# Misc.net
KiCad netlist of a schematic drawn in Altium Designer
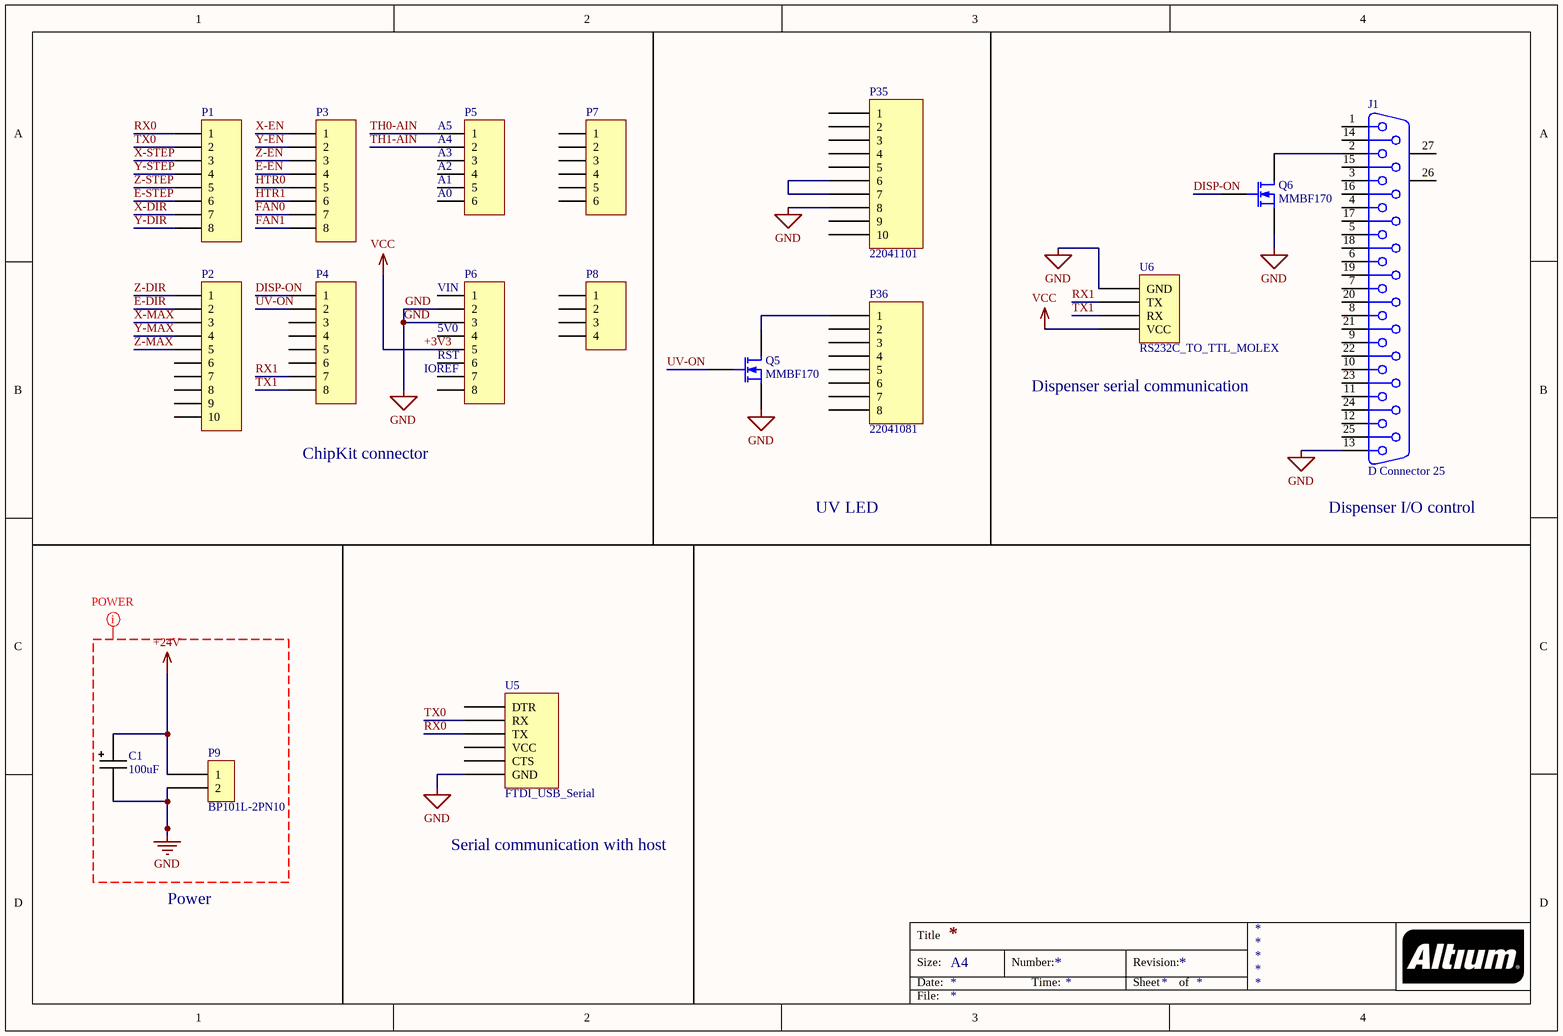
[diagram p0: Misc.SchDoc]

(export (version "E")
  (design (tool "Eeschema 10.0.6"))
  (components
    (comp (ref "C1")
      (value "Cap_alumi_electrolytic")
      (footprint "EEE-1HA101UP")
      (fields (field (name "ALTIUM_UNNAMED_1") "100uF"))
      (libsource (lib "3dprinter_shield") (part "Cap_alumi_electrolytic"))
    )
    (comp (ref "J1")
      (value "D Connector 25")
      (footprint "DSUB1.385-2H25A")
      (description "Receptacle Assembly, 25 Position, Right Angle")
      (fields (field (name "PUBLISHER") "Altium Limited"))
      (libsource (lib "Miscellaneous Connectors") (part "D Connector 25"))
    )
    (comp (ref "P1")
      (value "~")
      (footprint "HDR1X8")
      (description "Header, 8-Pin")
      (fields (field (name "PUBLISHER") "Altium Limited"))
      (libsource (lib "Miscellaneous Connectors") (part "Header 8"))
    )
    (comp (ref "P2")
      (value "~")
      (footprint "HDR1X10")
      (description "Header, 10-Pin")
      (fields (field (name "PUBLISHER") "Altium Limited"))
      (libsource (lib "Miscellaneous Connectors") (part "Header 10"))
    )
    (comp (ref "P3")
      (value "~")
      (footprint "HDR1X8")
      (description "Header, 8-Pin")
      (fields (field (name "PUBLISHER") "Altium Limited"))
      (libsource (lib "Miscellaneous Connectors") (part "Header 8"))
    )
    (comp (ref "P4")
      (value "~")
      (footprint "HDR1X8")
      (description "Header, 8-Pin")
      (fields (field (name "PUBLISHER") "Altium Limited"))
      (libsource (lib "Miscellaneous Connectors") (part "Header 8"))
    )
    (comp (ref "P5")
      (value "~")
      (footprint "HDR1X6")
      (description "Header, 6-Pin")
      (fields (field (name "PUBLISHER") "Altium Limited"))
      (libsource (lib "Miscellaneous Connectors") (part "Header 6"))
    )
    (comp (ref "P6")
      (value "~")
      (footprint "HDR1X8")
      (description "Header, 8-Pin")
      (fields (field (name "PUBLISHER") "Altium Limited"))
      (libsource (lib "Miscellaneous Connectors") (part "Header 8"))
    )
    (comp (ref "P7")
      (value "~")
      (footprint "HDR1X6")
      (description "Header, 6-Pin")
      (fields (field (name "PUBLISHER") "Altium Limited"))
      (libsource (lib "Miscellaneous Connectors") (part "Header 6"))
    )
    (comp (ref "P8")
      (value "Header 4")
      (footprint "HDR1X4")
      (description "Header, 4-Pin")
      (fields (field (name "PUBLISHER") "Altium Limited"))
      (libsource (lib "Miscellaneous Connectors") (part "Header 4"))
    )
    (comp (ref "P9")
      (value "BP101L-2PN10")
      (footprint "BP101L-2PN10")
      (libsource (lib "3dprinter_shield") (part "BP101L-2PN10"))
    )
    (comp (ref "P35")
      (value "22041101")
      (footprint "PHOENIX_10PIN_MOLEX")
      (libsource (lib "3dprinter_shield") (part "Phoenix_10pin_MOLEX"))
    )
    (comp (ref "P36")
      (value "22041081")
      (footprint "PHOENIX_8PIN_MOLEX")
      (libsource (lib "3dprinter_shield") (part "Phoenix_8pin_MOLEX"))
    )
    (comp (ref "Q5")
      (value "MMBF170")
      (footprint "MMBF170-SOT95P240X130-3N")
      (libsource (lib "3dprinter_shield") (part "MMBF170"))
    )
    (comp (ref "Q6")
      (value "MMBF170")
      (footprint "MMBF170-SOT95P240X130-3N")
      (libsource (lib "3dprinter_shield") (part "MMBF170"))
    )
    (comp (ref "U5")
      (value "FTDI_USB_Serial")
      (footprint "FTDI_USB_Serial")
      (libsource (lib "3dprinter_shield") (part "FTDI_USB_Serial"))
    )
    (comp (ref "U6")
      (value "RS232C_TO_TTL_MOLEX")
      (footprint "RS232C_TO_TTL_MOLEX")
      (libsource (lib "3dprinter_shield") (part "RS232C_TO_TTL_MOLEX"))
    )
  )
  (nets
    (net (code "1") (name "+24V") (class "Default")
      (node (ref "C1") (pin "2") (pinfunction "2_2") (pintype "passive"))
      (node (ref "P9") (pin "1") (pinfunction "1_1") (pintype "passive"))
    )
    (net (code "2") (name "/DISP-ON") (class "Default")
      (node (ref "P4") (pin "1") (pinfunction "1_1") (pintype "passive"))
      (node (ref "Q6") (pin "1") (pinfunction "G_1") (pintype "passive"))
    )
    (net (code "3") (name "/E-DIR") (class "Default")
      (node (ref "P2") (pin "2") (pinfunction "2_2") (pintype "passive"))
    )
    (net (code "4") (name "/E-EN") (class "Default")
      (node (ref "P3") (pin "4") (pinfunction "4_4") (pintype "passive"))
    )
    (net (code "5") (name "/E-STEP") (class "Default")
      (node (ref "P1") (pin "6") (pinfunction "6_6") (pintype "passive"))
    )
    (net (code "6") (name "/FAN0") (class "Default")
      (node (ref "P3") (pin "7") (pinfunction "7_7") (pintype "passive"))
    )
    (net (code "7") (name "/FAN1") (class "Default")
      (node (ref "P3") (pin "8") (pinfunction "8_8") (pintype "passive"))
    )
    (net (code "8") (name "/HTR0") (class "Default")
      (node (ref "P3") (pin "5") (pinfunction "5_5") (pintype "passive"))
    )
    (net (code "9") (name "/HTR1") (class "Default")
      (node (ref "P3") (pin "6") (pinfunction "6_6") (pintype "passive"))
    )
    (net (code "10") (name "/RX0") (class "Default")
      (node (ref "P1") (pin "1") (pinfunction "1_1") (pintype "passive"))
      (node (ref "U5") (pin "3") (pinfunction "TX_3") (pintype "passive"))
    )
    (net (code "11") (name "/RX1") (class "Default")
      (node (ref "P4") (pin "7") (pinfunction "7_7") (pintype "passive"))
      (node (ref "U6") (pin "TX") (pinfunction "TX_TX") (pintype "passive"))
    )
    (net (code "12") (name "/TH0-AIN") (class "Default")
      (node (ref "P5") (pin "1") (pinfunction "1_1") (pintype "passive"))
    )
    (net (code "13") (name "/TH1-AIN") (class "Default")
      (node (ref "P5") (pin "2") (pinfunction "2_2") (pintype "passive"))
    )
    (net (code "14") (name "/TX0") (class "Default")
      (node (ref "P1") (pin "2") (pinfunction "2_2") (pintype "passive"))
      (node (ref "U5") (pin "2") (pinfunction "RX_2") (pintype "passive"))
    )
    (net (code "15") (name "/TX1") (class "Default")
      (node (ref "P4") (pin "8") (pinfunction "8_8") (pintype "passive"))
      (node (ref "U6") (pin "RX") (pinfunction "RX_RX") (pintype "passive"))
    )
    (net (code "16") (name "/UV-ON") (class "Default")
      (node (ref "P4") (pin "2") (pinfunction "2_2") (pintype "passive"))
      (node (ref "Q5") (pin "1") (pinfunction "G_1") (pintype "passive"))
    )
    (net (code "17") (name "/X-DIR") (class "Default")
      (node (ref "P1") (pin "7") (pinfunction "7_7") (pintype "passive"))
    )
    (net (code "18") (name "/X-EN") (class "Default")
      (node (ref "P3") (pin "1") (pinfunction "1_1") (pintype "passive"))
    )
    (net (code "19") (name "/X-MAX") (class "Default")
      (node (ref "P2") (pin "3") (pinfunction "3_3") (pintype "passive"))
    )
    (net (code "20") (name "/X-STEP") (class "Default")
      (node (ref "P1") (pin "3") (pinfunction "3_3") (pintype "passive"))
    )
    (net (code "21") (name "/Y-DIR") (class "Default")
      (node (ref "P1") (pin "8") (pinfunction "8_8") (pintype "passive"))
    )
    (net (code "22") (name "/Y-EN") (class "Default")
      (node (ref "P3") (pin "2") (pinfunction "2_2") (pintype "passive"))
    )
    (net (code "23") (name "/Y-MAX") (class "Default")
      (node (ref "P2") (pin "4") (pinfunction "4_4") (pintype "passive"))
    )
    (net (code "24") (name "/Y-STEP") (class "Default")
      (node (ref "P1") (pin "4") (pinfunction "4_4") (pintype "passive"))
    )
    (net (code "25") (name "/Z-DIR") (class "Default")
      (node (ref "P2") (pin "1") (pinfunction "1_1") (pintype "passive"))
    )
    (net (code "26") (name "/Z-EN") (class "Default")
      (node (ref "P3") (pin "3") (pinfunction "3_3") (pintype "passive"))
    )
    (net (code "27") (name "/Z-MAX") (class "Default")
      (node (ref "P2") (pin "5") (pinfunction "5_5") (pintype "passive"))
    )
    (net (code "28") (name "/Z-STEP") (class "Default")
      (node (ref "P1") (pin "5") (pinfunction "5_5") (pintype "passive"))
    )
    (net (code "29") (name "GND") (class "Default")
      (node (ref "C1") (pin "1") (pinfunction "1_1") (pintype "passive"))
      (node (ref "J1") (pin "13") (pinfunction "13_13") (pintype "passive"))
      (node (ref "P35") (pin "8") (pinfunction "8_8") (pintype "passive"))
      (node (ref "P6") (pin "2") (pinfunction "2_2") (pintype "passive"))
      (node (ref "P6") (pin "3") (pinfunction "3_3") (pintype "passive"))
      (node (ref "P9") (pin "2") (pinfunction "2_2") (pintype "passive"))
      (node (ref "Q5") (pin "2") (pinfunction "S_2") (pintype "passive"))
      (node (ref "Q6") (pin "2") (pinfunction "S_2") (pintype "passive"))
      (node (ref "U5") (pin "6") (pinfunction "GND_6") (pintype "passive"))
      (node (ref "U6") (pin "GND") (pinfunction "GND_GND") (pintype "passive"))
    )
    (net (code "30") (name "Net-(P35-Pad6)") (class "Default")
      (node (ref "P35") (pin "6") (pinfunction "6_6") (pintype "passive"))
      (node (ref "P35") (pin "7") (pinfunction "7_7") (pintype "passive"))
    )
    (net (code "31") (name "Net-(Q5-D)") (class "Default")
      (node (ref "P36") (pin "1") (pinfunction "1_1") (pintype "passive"))
      (node (ref "Q5") (pin "3") (pinfunction "D_3") (pintype "passive"))
    )
    (net (code "32") (name "Net-(Q6-D)") (class "Default")
      (node (ref "J1") (pin "2") (pinfunction "2_2") (pintype "passive"))
      (node (ref "Q6") (pin "3") (pinfunction "D_3") (pintype "passive"))
    )
    (net (code "33") (name "VCC") (class "Default")
      (node (ref "P6") (pin "5") (pinfunction "5_5") (pintype "passive"))
      (node (ref "U6") (pin "VCC") (pinfunction "VCC_VCC") (pintype "passive"))
    )
    (net (code "34") (name "unconnected-(J1-MH1-Pad26)") (class "Default")
      (node (ref "J1") (pin "26") (pinfunction "MH1_26") (pintype "passive"))
    )
    (net (code "35") (name "unconnected-(J1-MH2-Pad27)") (class "Default")
      (node (ref "J1") (pin "27") (pinfunction "MH2_27") (pintype "passive"))
    )
    (net (code "36") (name "unconnected-(J1-Pad1)") (class "Default")
      (node (ref "J1") (pin "1") (pinfunction "1_1") (pintype "passive"))
    )
    (net (code "37") (name "unconnected-(J1-Pad3)") (class "Default")
      (node (ref "J1") (pin "3") (pinfunction "3_3") (pintype "passive"))
    )
    (net (code "38") (name "unconnected-(J1-Pad4)") (class "Default")
      (node (ref "J1") (pin "4") (pinfunction "4_4") (pintype "passive"))
    )
    (net (code "39") (name "unconnected-(J1-Pad5)") (class "Default")
      (node (ref "J1") (pin "5") (pinfunction "5_5") (pintype "passive"))
    )
    (net (code "40") (name "unconnected-(J1-Pad6)") (class "Default")
      (node (ref "J1") (pin "6") (pinfunction "6_6") (pintype "passive"))
    )
    (net (code "41") (name "unconnected-(J1-Pad7)") (class "Default")
      (node (ref "J1") (pin "7") (pinfunction "7_7") (pintype "passive"))
    )
    (net (code "42") (name "unconnected-(J1-Pad8)") (class "Default")
      (node (ref "J1") (pin "8") (pinfunction "8_8") (pintype "passive"))
    )
    (net (code "43") (name "unconnected-(J1-Pad9)") (class "Default")
      (node (ref "J1") (pin "9") (pinfunction "9_9") (pintype "passive"))
    )
    (net (code "44") (name "unconnected-(J1-Pad10)") (class "Default")
      (node (ref "J1") (pin "10") (pinfunction "10_10") (pintype "passive"))
    )
    (net (code "45") (name "unconnected-(J1-Pad11)") (class "Default")
      (node (ref "J1") (pin "11") (pinfunction "11_11") (pintype "passive"))
    )
    (net (code "46") (name "unconnected-(J1-Pad12)") (class "Default")
      (node (ref "J1") (pin "12") (pinfunction "12_12") (pintype "passive"))
    )
    (net (code "47") (name "unconnected-(J1-Pad14)") (class "Default")
      (node (ref "J1") (pin "14") (pinfunction "14_14") (pintype "passive"))
    )
    (net (code "48") (name "unconnected-(J1-Pad15)") (class "Default")
      (node (ref "J1") (pin "15") (pinfunction "15_15") (pintype "passive"))
    )
    (net (code "49") (name "unconnected-(J1-Pad16)") (class "Default")
      (node (ref "J1") (pin "16") (pinfunction "16_16") (pintype "passive"))
    )
    (net (code "50") (name "unconnected-(J1-Pad17)") (class "Default")
      (node (ref "J1") (pin "17") (pinfunction "17_17") (pintype "passive"))
    )
    (net (code "51") (name "unconnected-(J1-Pad18)") (class "Default")
      (node (ref "J1") (pin "18") (pinfunction "18_18") (pintype "passive"))
    )
    (net (code "52") (name "unconnected-(J1-Pad19)") (class "Default")
      (node (ref "J1") (pin "19") (pinfunction "19_19") (pintype "passive"))
    )
    (net (code "53") (name "unconnected-(J1-Pad20)") (class "Default")
      (node (ref "J1") (pin "20") (pinfunction "20_20") (pintype "passive"))
    )
    (net (code "54") (name "unconnected-(J1-Pad21)") (class "Default")
      (node (ref "J1") (pin "21") (pinfunction "21_21") (pintype "passive"))
    )
    (net (code "55") (name "unconnected-(J1-Pad22)") (class "Default")
      (node (ref "J1") (pin "22") (pinfunction "22_22") (pintype "passive"))
    )
    (net (code "56") (name "unconnected-(J1-Pad23)") (class "Default")
      (node (ref "J1") (pin "23") (pinfunction "23_23") (pintype "passive"))
    )
    (net (code "57") (name "unconnected-(J1-Pad24)") (class "Default")
      (node (ref "J1") (pin "24") (pinfunction "24_24") (pintype "passive"))
    )
    (net (code "58") (name "unconnected-(J1-Pad25)") (class "Default")
      (node (ref "J1") (pin "25") (pinfunction "25_25") (pintype "passive"))
    )
    (net (code "59") (name "unconnected-(P2-Pad6)") (class "Default")
      (node (ref "P2") (pin "6") (pinfunction "6_6") (pintype "passive"))
    )
    (net (code "60") (name "unconnected-(P2-Pad7)") (class "Default")
      (node (ref "P2") (pin "7") (pinfunction "7_7") (pintype "passive"))
    )
    (net (code "61") (name "unconnected-(P2-Pad8)") (class "Default")
      (node (ref "P2") (pin "8") (pinfunction "8_8") (pintype "passive"))
    )
    (net (code "62") (name "unconnected-(P2-Pad9)") (class "Default")
      (node (ref "P2") (pin "9") (pinfunction "9_9") (pintype "passive"))
    )
    (net (code "63") (name "unconnected-(P2-Pad10)") (class "Default")
      (node (ref "P2") (pin "10") (pinfunction "10_10") (pintype "passive"))
    )
    (net (code "64") (name "unconnected-(P4-Pad3)") (class "Default")
      (node (ref "P4") (pin "3") (pinfunction "3_3") (pintype "passive"))
    )
    (net (code "65") (name "unconnected-(P4-Pad4)") (class "Default")
      (node (ref "P4") (pin "4") (pinfunction "4_4") (pintype "passive"))
    )
    (net (code "66") (name "unconnected-(P4-Pad5)") (class "Default")
      (node (ref "P4") (pin "5") (pinfunction "5_5") (pintype "passive"))
    )
    (net (code "67") (name "unconnected-(P4-Pad6)") (class "Default")
      (node (ref "P4") (pin "6") (pinfunction "6_6") (pintype "passive"))
    )
    (net (code "68") (name "unconnected-(P5-Pad3)") (class "Default")
      (node (ref "P5") (pin "3") (pinfunction "3_3") (pintype "passive"))
    )
    (net (code "69") (name "unconnected-(P5-Pad4)") (class "Default")
      (node (ref "P5") (pin "4") (pinfunction "4_4") (pintype "passive"))
    )
    (net (code "70") (name "unconnected-(P5-Pad5)") (class "Default")
      (node (ref "P5") (pin "5") (pinfunction "5_5") (pintype "passive"))
    )
    (net (code "71") (name "unconnected-(P5-Pad6)") (class "Default")
      (node (ref "P5") (pin "6") (pinfunction "6_6") (pintype "passive"))
    )
    (net (code "72") (name "unconnected-(P6-Pad1)") (class "Default")
      (node (ref "P6") (pin "1") (pinfunction "1_1") (pintype "passive"))
    )
    (net (code "73") (name "unconnected-(P6-Pad4)") (class "Default")
      (node (ref "P6") (pin "4") (pinfunction "4_4") (pintype "passive"))
    )
    (net (code "74") (name "unconnected-(P6-Pad6)") (class "Default")
      (node (ref "P6") (pin "6") (pinfunction "6_6") (pintype "passive"))
    )
    (net (code "75") (name "unconnected-(P6-Pad7)") (class "Default")
      (node (ref "P6") (pin "7") (pinfunction "7_7") (pintype "passive"))
    )
    (net (code "76") (name "unconnected-(P6-Pad8)") (class "Default")
      (node (ref "P6") (pin "8") (pinfunction "8_8") (pintype "passive"))
    )
    (net (code "77") (name "unconnected-(P7-Pad1)") (class "Default")
      (node (ref "P7") (pin "1") (pinfunction "1_1") (pintype "passive"))
    )
    (net (code "78") (name "unconnected-(P7-Pad2)") (class "Default")
      (node (ref "P7") (pin "2") (pinfunction "2_2") (pintype "passive"))
    )
    (net (code "79") (name "unconnected-(P7-Pad3)") (class "Default")
      (node (ref "P7") (pin "3") (pinfunction "3_3") (pintype "passive"))
    )
    (net (code "80") (name "unconnected-(P7-Pad4)") (class "Default")
      (node (ref "P7") (pin "4") (pinfunction "4_4") (pintype "passive"))
    )
    (net (code "81") (name "unconnected-(P7-Pad5)") (class "Default")
      (node (ref "P7") (pin "5") (pinfunction "5_5") (pintype "passive"))
    )
    (net (code "82") (name "unconnected-(P7-Pad6)") (class "Default")
      (node (ref "P7") (pin "6") (pinfunction "6_6") (pintype "passive"))
    )
    (net (code "83") (name "unconnected-(P8-Pad1)") (class "Default")
      (node (ref "P8") (pin "1") (pinfunction "1_1") (pintype "passive"))
    )
    (net (code "84") (name "unconnected-(P8-Pad2)") (class "Default")
      (node (ref "P8") (pin "2") (pinfunction "2_2") (pintype "passive"))
    )
    (net (code "85") (name "unconnected-(P8-Pad3)") (class "Default")
      (node (ref "P8") (pin "3") (pinfunction "3_3") (pintype "passive"))
    )
    (net (code "86") (name "unconnected-(P8-Pad4)") (class "Default")
      (node (ref "P8") (pin "4") (pinfunction "4_4") (pintype "passive"))
    )
    (net (code "87") (name "unconnected-(P35-Pad1)") (class "Default")
      (node (ref "P35") (pin "1") (pinfunction "1_1") (pintype "passive"))
    )
    (net (code "88") (name "unconnected-(P35-Pad2)") (class "Default")
      (node (ref "P35") (pin "2") (pinfunction "2_2") (pintype "passive"))
    )
    (net (code "89") (name "unconnected-(P35-Pad3)") (class "Default")
      (node (ref "P35") (pin "3") (pinfunction "3_3") (pintype "passive"))
    )
    (net (code "90") (name "unconnected-(P35-Pad4)") (class "Default")
      (node (ref "P35") (pin "4") (pinfunction "4_4") (pintype "passive"))
    )
    (net (code "91") (name "unconnected-(P35-Pad5)") (class "Default")
      (node (ref "P35") (pin "5") (pinfunction "5_5") (pintype "passive"))
    )
    (net (code "92") (name "unconnected-(P35-Pad9)") (class "Default")
      (node (ref "P35") (pin "9") (pinfunction "9_9") (pintype "passive"))
    )
    (net (code "93") (name "unconnected-(P35-Pad10)") (class "Default")
      (node (ref "P35") (pin "10") (pinfunction "10_10") (pintype "passive"))
    )
    (net (code "94") (name "unconnected-(P36-Pad2)") (class "Default")
      (node (ref "P36") (pin "2") (pinfunction "2_2") (pintype "passive"))
    )
    (net (code "95") (name "unconnected-(P36-Pad3)") (class "Default")
      (node (ref "P36") (pin "3") (pinfunction "3_3") (pintype "passive"))
    )
    (net (code "96") (name "unconnected-(P36-Pad4)") (class "Default")
      (node (ref "P36") (pin "4") (pinfunction "4_4") (pintype "passive"))
    )
    (net (code "97") (name "unconnected-(P36-Pad5)") (class "Default")
      (node (ref "P36") (pin "5") (pinfunction "5_5") (pintype "passive"))
    )
    (net (code "98") (name "unconnected-(P36-Pad6)") (class "Default")
      (node (ref "P36") (pin "6") (pinfunction "6_6") (pintype "passive"))
    )
    (net (code "99") (name "unconnected-(P36-Pad7)") (class "Default")
      (node (ref "P36") (pin "7") (pinfunction "7_7") (pintype "passive"))
    )
    (net (code "100") (name "unconnected-(P36-Pad8)") (class "Default")
      (node (ref "P36") (pin "8") (pinfunction "8_8") (pintype "passive"))
    )
    (net (code "101") (name "unconnected-(U5-CTS-Pad5)") (class "Default")
      (node (ref "U5") (pin "5") (pinfunction "CTS_5") (pintype "passive"))
    )
    (net (code "102") (name "unconnected-(U5-DTR-Pad1)") (class "Default")
      (node (ref "U5") (pin "1") (pinfunction "DTR_1") (pintype "passive"))
    )
    (net (code "103") (name "unconnected-(U5-VCC-Pad4)") (class "Default")
      (node (ref "U5") (pin "4") (pinfunction "VCC_4") (pintype "passive"))
    )
  )
)
